# Sheet.net
KiCad netlist of a schematic drawn in Altium Designer
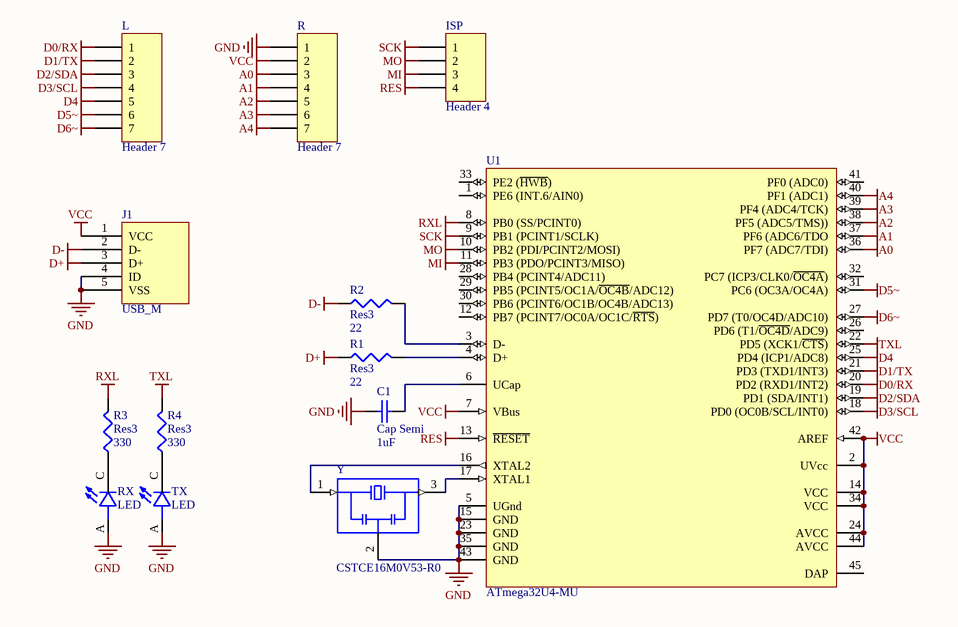
[diagram p0: Sheet.SchDoc]

(export (version "E")
  (design (tool "Eeschema 10.0.6"))
  (components
    (comp (ref "C1")
      (value "Cap Semi")
      (footprint "1608[0603]")
      (description "Capacitor (Semiconductor SIM Model)")
      (fields (field (name "ALTIUM_VALUE") "1uF") (field (name "PUBLISHER") "Altium Limited"))
      (libsource (lib "Miscellaneous Devices") (part "Cap Semi"))
    )
    (comp (ref "ISP")
      (value "Header 4")
      (footprint "HDR1X4")
      (description "Header, 4-Pin")
      (fields (field (name "PUBLISHER") "Altium Limited"))
      (libsource (lib "Miscellaneous Connectors") (part "Header 4"))
    )
    (comp (ref "J1")
      (value "USB_M")
      (footprint "USB_MICRO")
      (description "MicroUSB諉諳")
      (libsource (lib "Fszhang") (part "USB_M"))
    )
    (comp (ref "L")
      (value "Header 7")
      (footprint "HDR1X7")
      (description "Header, 7-Pin")
      (fields (field (name "PUBLISHER") "Altium Limited"))
      (libsource (lib "Miscellaneous Connectors") (part "Header 7"))
    )
    (comp (ref "R")
      (value "Header 7")
      (footprint "HDR1X7")
      (description "Header, 7-Pin")
      (fields (field (name "PUBLISHER") "Altium Limited"))
      (libsource (lib "Miscellaneous Connectors") (part "Header 7"))
    )
    (comp (ref "R1")
      (value "Res3")
      (footprint "J1-0603")
      (description "Resistor")
      (fields (field (name "ALTIUM_VALUE") "22") (field (name "PUBLISHER") "Altium Limited"))
      (libsource (lib "Miscellaneous Devices") (part "Res3"))
    )
    (comp (ref "R2")
      (value "Res3")
      (footprint "J1-0603")
      (description "Resistor")
      (fields (field (name "ALTIUM_VALUE") "22") (field (name "PUBLISHER") "Altium Limited"))
      (libsource (lib "Miscellaneous Devices") (part "Res3"))
    )
    (comp (ref "R3")
      (value "Res3")
      (footprint "J1-0603")
      (description "Resistor")
      (fields (field (name "ALTIUM_VALUE") "330") (field (name "PUBLISHER") "Altium Limited"))
      (libsource (lib "Miscellaneous Devices") (part "Res3"))
    )
    (comp (ref "R4")
      (value "Res3")
      (footprint "J1-0603")
      (description "Resistor")
      (fields (field (name "ALTIUM_VALUE") "330") (field (name "PUBLISHER") "Altium Limited"))
      (libsource (lib "Miscellaneous Devices") (part "Res3"))
    )
    (comp (ref "RX")
      (value "LED")
      (footprint "LEDC1608X65N")
      (description "White LED Indication - Discrete 3.1V 0603 _1608 Metric_")
      (fields (field (name "MP") "LTW-C191TLA") (field (name "MF") "Lite-On"))
      (libsource (lib "LTW-C191TLA") (part "LTW-C191TLA"))
    )
    (comp (ref "TX")
      (value "LED")
      (footprint "LEDC1608X65N")
      (description "White LED Indication - Discrete 3.1V 0603 _1608 Metric_")
      (fields (field (name "MP") "LTW-C191TLA") (field (name "MF") "Lite-On"))
      (libsource (lib "LTW-C191TLA") (part "LTW-C191TLA"))
    )
    (comp (ref "U1")
      (value "ATmega32U4-MU")
      (footprint "44PW_N")
      (fields (field (name "PUBLISHER") "Altium Limited"))
      (libsource (lib "Atmel Microcontroller 8-Bit megaAVR") (part "ATmega32U4-MU"))
    )
    (comp (ref "Y")
      (value "CSTCE16M0V53-R0")
      (footprint "OSC_CSTCE16M0V53-R0")
      (description "16MHz Ceramic Resonator Built in Capacitor 15pF Â±0.3% -20Â°C ~ 80Â°C Surface Mount")
      (fields (field (name "MF") "Murata"))
      (libsource (lib "CSTCE16M0V53-R0") (part "CSTCE16M0V53-R0"))
    )
  )
  (nets
    (net (code "1") (name "A0") (class "Default")
      (node (ref "R") (pin "3") (pinfunction "3_3") (pintype "passive"))
      (node (ref "U1") (pin "36") (pinfunction "PF7_(ADC7/TDI)_36") (pintype "bidirectional"))
    )
    (net (code "2") (name "A1") (class "Default")
      (node (ref "R") (pin "4") (pinfunction "4_4") (pintype "passive"))
      (node (ref "U1") (pin "37") (pinfunction "PF6_(ADC6/TDO_37") (pintype "bidirectional"))
    )
    (net (code "3") (name "A2") (class "Default")
      (node (ref "R") (pin "5") (pinfunction "5_5") (pintype "passive"))
      (node (ref "U1") (pin "38") (pinfunction "PF5_(ADC5/TMS))_38") (pintype "bidirectional"))
    )
    (net (code "4") (name "A3") (class "Default")
      (node (ref "R") (pin "6") (pinfunction "6_6") (pintype "passive"))
      (node (ref "U1") (pin "39") (pinfunction "PF4_(ADC4/TCK)_39") (pintype "bidirectional"))
    )
    (net (code "5") (name "A4") (class "Default")
      (node (ref "R") (pin "7") (pinfunction "7_7") (pintype "passive"))
      (node (ref "U1") (pin "40") (pinfunction "PF1_(ADC1)_40") (pintype "bidirectional"))
    )
    (net (code "6") (name "D+") (class "Default")
      (node (ref "J1") (pin "3") (pinfunction "D+_3") (pintype "passive"))
      (node (ref "R1") (pin "1") (pinfunction "1_1") (pintype "passive"))
    )
    (net (code "7") (name "D-") (class "Default")
      (node (ref "J1") (pin "2") (pinfunction "D-_2") (pintype "passive"))
      (node (ref "R2") (pin "1") (pinfunction "1_1") (pintype "passive"))
    )
    (net (code "8") (name "D0{slash}RX") (class "Default")
      (node (ref "L") (pin "1") (pinfunction "1_1") (pintype "passive"))
      (node (ref "U1") (pin "20") (pinfunction "PD2_(RXD1/INT2)_20") (pintype "bidirectional"))
    )
    (net (code "9") (name "D1{slash}TX") (class "Default")
      (node (ref "L") (pin "2") (pinfunction "2_2") (pintype "passive"))
      (node (ref "U1") (pin "21") (pinfunction "PD3_(TXD1/INT3)_21") (pintype "bidirectional"))
    )
    (net (code "10") (name "D2{slash}SDA") (class "Default")
      (node (ref "L") (pin "3") (pinfunction "3_3") (pintype "passive"))
      (node (ref "U1") (pin "19") (pinfunction "PD1_(SDA/INT1)_19") (pintype "bidirectional"))
    )
    (net (code "11") (name "D3{slash}SCL") (class "Default")
      (node (ref "L") (pin "4") (pinfunction "4_4") (pintype "passive"))
      (node (ref "U1") (pin "18") (pinfunction "PD0_(OC0B/SCL/INT0)_18") (pintype "bidirectional"))
    )
    (net (code "12") (name "D4") (class "Default")
      (node (ref "L") (pin "5") (pinfunction "5_5") (pintype "passive"))
      (node (ref "U1") (pin "25") (pinfunction "PD4_(ICP1/ADC8)_25") (pintype "bidirectional"))
    )
    (net (code "13") (name "D5~") (class "Default")
      (node (ref "L") (pin "6") (pinfunction "6_6") (pintype "passive"))
      (node (ref "U1") (pin "31") (pinfunction "PC6_(OC3A/OC4A)_31") (pintype "bidirectional"))
    )
    (net (code "14") (name "D6~") (class "Default")
      (node (ref "L") (pin "7") (pinfunction "7_7") (pintype "passive"))
      (node (ref "U1") (pin "27") (pinfunction "PD7_(T0/OC4D/ADC10)_27") (pintype "bidirectional"))
    )
    (net (code "15") (name "GND") (class "Default")
      (node (ref "C1") (pin "1") (pinfunction "1_1") (pintype "passive"))
      (node (ref "J1") (pin "4") (pinfunction "ID_4") (pintype "passive"))
      (node (ref "J1") (pin "5") (pinfunction "VSS_5") (pintype "passive"))
      (node (ref "R") (pin "1") (pinfunction "1_1") (pintype "passive"))
      (node (ref "RX") (pin "A") (pinfunction "A_A") (pintype "passive"))
      (node (ref "TX") (pin "A") (pinfunction "A_A") (pintype "passive"))
      (node (ref "U1") (pin "15") (pinfunction "GND_15") (pintype "power_in"))
      (node (ref "U1") (pin "23") (pinfunction "GND_23") (pintype "power_in"))
      (node (ref "U1") (pin "35") (pinfunction "GND_35") (pintype "power_in"))
      (node (ref "U1") (pin "43") (pinfunction "GND_43") (pintype "power_in"))
      (node (ref "U1") (pin "5") (pinfunction "UGnd_5") (pintype "power_in"))
      (node (ref "Y") (pin "2") (pinfunction "GND_2") (pintype "power_in"))
    )
    (net (code "16") (name "MI") (class "Default")
      (node (ref "ISP") (pin "3") (pinfunction "3_3") (pintype "passive"))
      (node (ref "U1") (pin "11") (pinfunction "PB3_(PDO/PCINT3/MISO)_11") (pintype "bidirectional"))
    )
    (net (code "17") (name "MO") (class "Default")
      (node (ref "ISP") (pin "2") (pinfunction "2_2") (pintype "passive"))
      (node (ref "U1") (pin "10") (pinfunction "PB2_(PDI/PCINT2/MOSI)_10") (pintype "bidirectional"))
    )
    (net (code "18") (name "Net-(R3-Pad1)") (class "Default")
      (node (ref "R3") (pin "1") (pinfunction "1_1") (pintype "passive"))
      (node (ref "RX") (pin "C") (pinfunction "C_C") (pintype "passive"))
    )
    (net (code "19") (name "Net-(R4-Pad1)") (class "Default")
      (node (ref "R4") (pin "1") (pinfunction "1_1") (pintype "passive"))
      (node (ref "TX") (pin "C") (pinfunction "C_C") (pintype "passive"))
    )
    (net (code "20") (name "Net-(U1-D+)") (class "Default")
      (node (ref "R1") (pin "2") (pinfunction "2_2") (pintype "passive"))
      (node (ref "U1") (pin "4") (pinfunction "D+_4") (pintype "bidirectional"))
    )
    (net (code "21") (name "Net-(U1-D-)") (class "Default")
      (node (ref "R2") (pin "2") (pinfunction "2_2") (pintype "passive"))
      (node (ref "U1") (pin "3") (pinfunction "D-_3") (pintype "bidirectional"))
    )
    (net (code "22") (name "Net-(U1-UCap)") (class "Default")
      (node (ref "C1") (pin "2") (pinfunction "2_2") (pintype "passive"))
      (node (ref "U1") (pin "6") (pinfunction "UCap_6") (pintype "passive"))
    )
    (net (code "23") (name "Net-(U1-XTAL1)") (class "Default")
      (node (ref "U1") (pin "17") (pinfunction "XTAL1_17") (pintype "input"))
      (node (ref "Y") (pin "3") (pinfunction "OUT_3") (pintype "output"))
    )
    (net (code "24") (name "Net-(U1-XTAL2)") (class "Default")
      (node (ref "U1") (pin "16") (pinfunction "XTAL2_16") (pintype "output"))
      (node (ref "Y") (pin "1") (pinfunction "IN_1") (pintype "input"))
    )
    (net (code "25") (name "RES") (class "Default")
      (node (ref "ISP") (pin "4") (pinfunction "4_4") (pintype "passive"))
      (node (ref "U1") (pin "13") (pinfunction "~{RESET}_13") (pintype "input"))
    )
    (net (code "26") (name "RXL") (class "Default")
      (node (ref "R3") (pin "2") (pinfunction "2_2") (pintype "passive"))
      (node (ref "U1") (pin "8") (pinfunction "PB0_(SS/PCINT0)_8") (pintype "bidirectional"))
    )
    (net (code "27") (name "SCK") (class "Default")
      (node (ref "ISP") (pin "1") (pinfunction "1_1") (pintype "passive"))
      (node (ref "U1") (pin "9") (pinfunction "PB1_(PCINT1/SCLK)_9") (pintype "bidirectional"))
    )
    (net (code "28") (name "TXL") (class "Default")
      (node (ref "R4") (pin "2") (pinfunction "2_2") (pintype "passive"))
      (node (ref "U1") (pin "22") (pinfunction "PD5_(XCK1/~{CTS})_22") (pintype "bidirectional"))
    )
    (net (code "29") (name "VCC") (class "Default")
      (node (ref "J1") (pin "1") (pinfunction "VCC_1") (pintype "passive"))
      (node (ref "R") (pin "2") (pinfunction "2_2") (pintype "passive"))
      (node (ref "U1") (pin "14") (pinfunction "VCC_14") (pintype "power_in"))
      (node (ref "U1") (pin "2") (pinfunction "UVcc_2") (pintype "power_in"))
      (node (ref "U1") (pin "24") (pinfunction "AVCC_24") (pintype "power_in"))
      (node (ref "U1") (pin "34") (pinfunction "VCC_34") (pintype "power_in"))
      (node (ref "U1") (pin "42") (pinfunction "AREF_42") (pintype "input"))
      (node (ref "U1") (pin "44") (pinfunction "AVCC_44") (pintype "power_in"))
      (node (ref "U1") (pin "7") (pinfunction "VBus_7") (pintype "input"))
    )
    (net (code "30") (name "unconnected-(U1-DAP-Pad45)") (class "Default")
      (node (ref "U1") (pin "45") (pinfunction "DAP_45") (pintype "power_in"))
    )
    (net (code "31") (name "unconnected-(U1-PB4_(PCINT4{slash}ADC11)-Pad28)") (class "Default")
      (node (ref "U1") (pin "28") (pinfunction "PB4_(PCINT4/ADC11)_28") (pintype "bidirectional"))
    )
    (net (code "32") (name "unconnected-(U1-PB5_(PCINT5{slash}OC1A{slash}~{OC4B}{slash}ADC12)-Pad29)") (class "Default")
      (node (ref "U1") (pin "29") (pinfunction "PB5_(PCINT5/OC1A/~{OC4B}/ADC12)_29") (pintype "bidirectional"))
    )
    (net (code "33") (name "unconnected-(U1-PB6_(PCINT6{slash}OC1B{slash}OC4B{slash}ADC13)-Pad30)") (class "Default")
      (node (ref "U1") (pin "30") (pinfunction "PB6_(PCINT6/OC1B/OC4B/ADC13)_30") (pintype "bidirectional"))
    )
    (net (code "34") (name "unconnected-(U1-PB7_(PCINT7{slash}OC0A{slash}OC1C{slash}~{RTS})-Pad12)") (class "Default")
      (node (ref "U1") (pin "12") (pinfunction "PB7_(PCINT7/OC0A/OC1C/~{RTS})_12") (pintype "bidirectional"))
    )
    (net (code "35") (name "unconnected-(U1-PC7_(ICP3{slash}CLK0{slash}~{OC4A})-Pad32)") (class "Default")
      (node (ref "U1") (pin "32") (pinfunction "PC7_(ICP3/CLK0/~{OC4A})_32") (pintype "bidirectional"))
    )
    (net (code "36") (name "unconnected-(U1-PD6_(T1{slash}~{OC4D}{slash}ADC9)-Pad26)") (class "Default")
      (node (ref "U1") (pin "26") (pinfunction "PD6_(T1/~{OC4D}/ADC9)_26") (pintype "bidirectional"))
    )
    (net (code "37") (name "unconnected-(U1-PE2_(~{HWB})-Pad33)") (class "Default")
      (node (ref "U1") (pin "33") (pinfunction "PE2_(~{HWB})_33") (pintype "bidirectional"))
    )
    (net (code "38") (name "unconnected-(U1-PE6_(INT.6{slash}AIN0)-Pad1)") (class "Default")
      (node (ref "U1") (pin "1") (pinfunction "PE6_(INT.6/AIN0)_1") (pintype "bidirectional"))
    )
    (net (code "39") (name "unconnected-(U1-PF0_(ADC0)-Pad41)") (class "Default")
      (node (ref "U1") (pin "41") (pinfunction "PF0_(ADC0)_41") (pintype "bidirectional"))
    )
  )
)
